# TPS61032.net
KiCad netlist of a schematic drawn in EAGLE
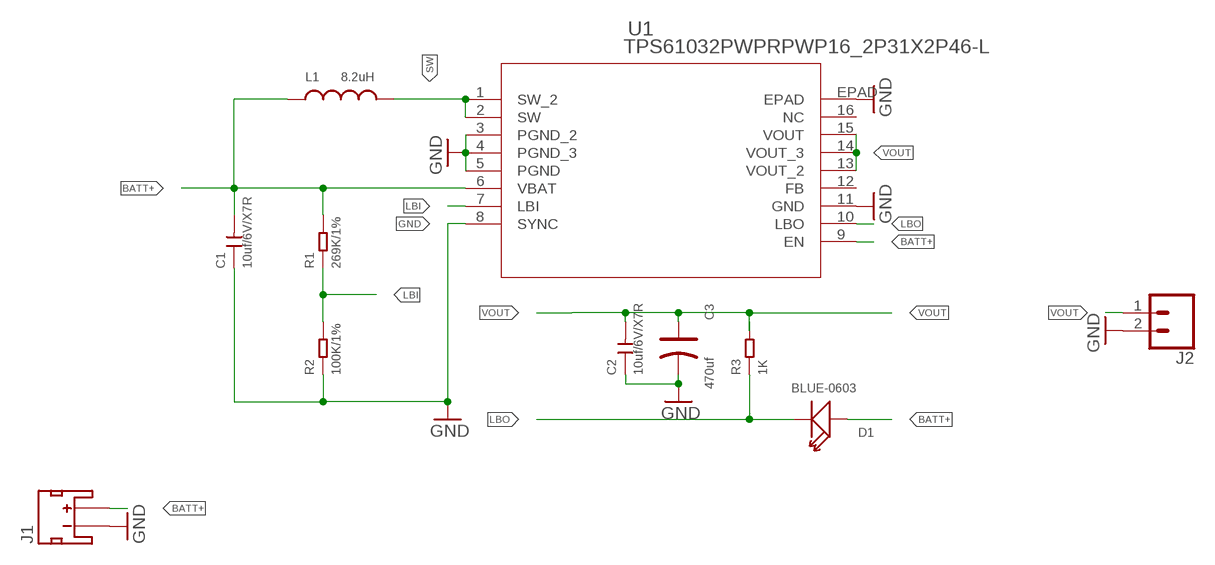
[diagram p0: schematic, sheet 1]

(export (version "E")
  (design (tool "Eeschema 10.0.6"))
  (components
    (comp (ref "C1")
      (value "10uf/6V/X7R")
      (footprint "eagle-import:C0805")
      (fields (field (name "MPN") "CC0805ZKY5V6BB106"))
      (libsource (lib "eagle-import") (part "CERAMIC-10UF-10V-(-20%～+80%)-Y5V(0805)"))
    )
    (comp (ref "C2")
      (value "10uf/6V/X7R")
      (footprint "eagle-import:C0805")
      (fields (field (name "MPN") "CC0805ZKY5V6BB106"))
      (libsource (lib "eagle-import") (part "CERAMIC-10UF-10V-(-20%～+80%)-Y5V(0805)"))
    )
    (comp (ref "C3")
      (value "470uf")
      (footprint "eagle-import:AVX-D")
      (fields (field (name "MPN") "TAJD477*006#NJ"))
      (libsource (lib "eagle-import") (part "TANTALUM-SMD-470UF-6.3V(AVX-D)"))
    )
    (comp (ref "D1")
      (value "BLUE-0603")
      (footprint "eagle-import:LED-0603")
      (fields (field (name "MPN") "19-217-BHC-ZL1M2RY-3T"))
      (libsource (lib "eagle-import") (part "SMD-LED-CLEAR-BLUE(0603)"))
    )
    (comp (ref "J1")
      (value "JST_2MM_MALE")
      (footprint "eagle-import:JST-2-SMD")
      (libsource (lib "eagle-import") (part "JST_2MM_MALE"))
    )
    (comp (ref "J2")
      (value "CONN_02PTH4")
      (footprint "eagle-import:1X02_XTRA_BIG")
      (libsource (lib "eagle-import") (part "CONN_02PTH4"))
    )
    (comp (ref "L1")
      (value "8.2uH")
      (footprint "eagle-import:7443550820")
      (libsource (lib "eagle-import") (part "LWE-HCI-13MM"))
    )
    (comp (ref "R1")
      (value "269K/1%")
      (footprint "eagle-import:R0805")
      (fields (field (name "MPN") "RC0805JR-07220RL"))
      (libsource (lib "eagle-import") (part "SMD-RES-220R-5%-1/8W(0805)"))
    )
    (comp (ref "R2")
      (value "100K/1%")
      (footprint "eagle-import:R0805")
      (fields (field (name "MPN") "RC0805JR-07220RL"))
      (libsource (lib "eagle-import") (part "SMD-RES-220R-5%-1/8W(0805)"))
    )
    (comp (ref "R3")
      (value "1K")
      (footprint "eagle-import:R0603")
      (fields (field (name "MPN") "RC0603FR-071KL"))
      (libsource (lib "eagle-import") (part "SMD-RES-1K-1%-1/10W(0603)"))
    )
    (comp (ref "U1")
      (value "TPS61032PWPRPWP16_2P31X2P46-L")
      (footprint "eagle-import:PWP16_2P31X2P46-L")
      (fields (field (name "MANUFACTURER_PART_NUMBER") "TPS61032PWPR"))
      (libsource (lib "eagle-import") (part "TPS61032PWPRPWP16_2P31X2P46-L"))
    )
  )
  (nets
    (net (code "1") (name "BATT+") (class "Default")
      (node (ref "C1") (pin "2") (pinfunction "2_2") (pintype "passive"))
      (node (ref "D1") (pin "+") (pinfunction "+_+") (pintype "passive"))
      (node (ref "J1") (pin "2") (pinfunction "+_2") (pintype "bidirectional"))
      (node (ref "L1") (pin "1") (pinfunction "1_1") (pintype "bidirectional"))
      (node (ref "R1") (pin "2") (pinfunction "2_2") (pintype "passive"))
      (node (ref "U1") (pin "6") (pinfunction "VBAT_6") (pintype "input"))
      (node (ref "U1") (pin "9") (pinfunction "EN_9") (pintype "input"))
    )
    (net (code "2") (name "GND") (class "Default")
      (node (ref "C1") (pin "1") (pinfunction "1_1") (pintype "passive"))
      (node (ref "C2") (pin "1") (pinfunction "1_1") (pintype "passive"))
      (node (ref "C3") (pin "-") (pinfunction "-_-") (pintype "passive"))
      (node (ref "J1") (pin "1") (pinfunction "-_1") (pintype "bidirectional"))
      (node (ref "J2") (pin "2") (pinfunction "2_2") (pintype "passive"))
      (node (ref "R2") (pin "1") (pinfunction "1_1") (pintype "passive"))
      (node (ref "U1") (pin "11") (pinfunction "GND_11") (pintype "bidirectional"))
      (node (ref "U1") (pin "3") (pinfunction "PGND_2_3") (pintype "bidirectional"))
      (node (ref "U1") (pin "4") (pinfunction "PGND_3_4") (pintype "bidirectional"))
      (node (ref "U1") (pin "5") (pinfunction "PGND_5") (pintype "bidirectional"))
      (node (ref "U1") (pin "8") (pinfunction "SYNC_8") (pintype "input"))
      (node (ref "U1") (pin "EPAD") (pinfunction "EPAD_EPAD") (pintype "passive"))
    )
    (net (code "3") (name "LBI") (class "Default")
      (node (ref "R1") (pin "1") (pinfunction "1_1") (pintype "passive"))
      (node (ref "R2") (pin "2") (pinfunction "2_2") (pintype "passive"))
      (node (ref "U1") (pin "7") (pinfunction "LBI_7") (pintype "input"))
    )
    (net (code "4") (name "LBO") (class "Default")
      (node (ref "D1") (pin "-") (pinfunction "-_-") (pintype "passive"))
      (node (ref "R3") (pin "1") (pinfunction "1_1") (pintype "passive"))
      (node (ref "U1") (pin "10") (pinfunction "LBO_10") (pintype "output"))
    )
    (net (code "5") (name "SW") (class "Default")
      (node (ref "L1") (pin "2") (pinfunction "2_2") (pintype "bidirectional"))
      (node (ref "U1") (pin "1") (pinfunction "SW_2_1") (pintype "input"))
      (node (ref "U1") (pin "2") (pinfunction "SW_2") (pintype "input"))
    )
    (net (code "6") (name "VOUT") (class "Default")
      (node (ref "C2") (pin "2") (pinfunction "2_2") (pintype "passive"))
      (node (ref "C3") (pin "+") (pinfunction "+_+") (pintype "passive"))
      (node (ref "J2") (pin "1") (pinfunction "1_1") (pintype "passive"))
      (node (ref "R3") (pin "2") (pinfunction "2_2") (pintype "passive"))
      (node (ref "U1") (pin "13") (pinfunction "VOUT_2_13") (pintype "output"))
      (node (ref "U1") (pin "14") (pinfunction "VOUT_3_14") (pintype "output"))
      (node (ref "U1") (pin "15") (pinfunction "VOUT_15") (pintype "output"))
    )
    (net (code "7") (name "unconnected-(J1-PAD1-PadNC1)") (class "Default")
      (node (ref "J1") (pin "NC1") (pinfunction "PAD1_NC1") (pintype "bidirectional"))
    )
    (net (code "8") (name "unconnected-(J1-PAD2-PadNC2)") (class "Default")
      (node (ref "J1") (pin "NC2") (pinfunction "PAD2_NC2") (pintype "bidirectional"))
    )
    (net (code "9") (name "unconnected-(U1-FB-Pad12)") (class "Default")
      (node (ref "U1") (pin "12") (pinfunction "FB_12") (pintype "input"))
    )
    (net (code "10") (name "unconnected-(U1-NC-Pad16)") (class "Default")
      (node (ref "U1") (pin "16") (pinfunction "NC_16") (pintype "passive"))
    )
  )
)
